# C_376p667.net
KiCad netlist of a schematic drawn in Altium Designer
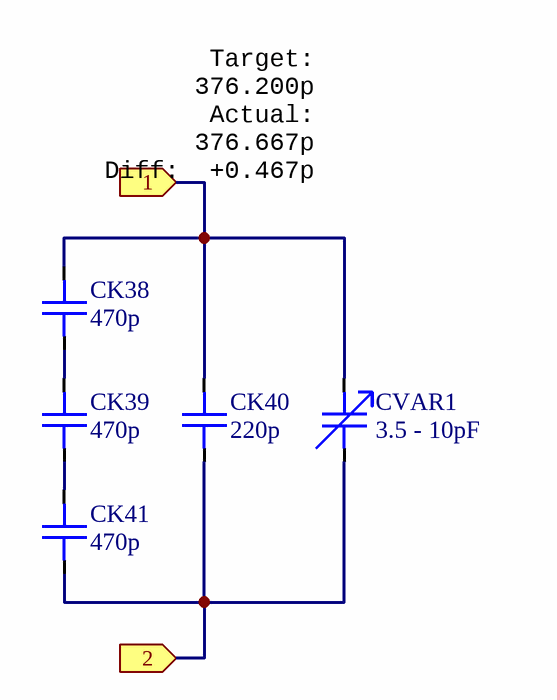
[diagram p0: C_376p667.SchDoc]

(export (version "E")
  (design (tool "Eeschema 10.0.6"))
  (components
    (comp (ref "CK38")
      (value "470p")
      (footprint "CAPC1005X06N(SMC0402)")
      (description "C; 470p; 50V; 1%; NP0/C0G; ??;")
      (fields (field (name "MANUFACTURER") "Kemet: C0402C471F5GAC7867;;Murata: GRM1555C1H471FA01D"))
      (libsource (lib "altium_sql") (part "CK"))
    )
    (comp (ref "CK39")
      (value "470p")
      (footprint "CAPC1005X06N(SMC0402)")
      (description "C; 470p; 50V; 1%; NP0/C0G; ??;")
      (fields (field (name "MANUFACTURER") "Kemet: C0402C471F5GAC7867;;Murata: GRM1555C1H471FA01D"))
      (libsource (lib "altium_sql") (part "CK"))
    )
    (comp (ref "CK40")
      (value "220p")
      (footprint "CAPC1005X06N(SMC0402)")
      (description "C; 220p; 50V; 1%; NP0/C0G; ??;")
      (fields (field (name "MANUFACTURER") "YAGEO: CC0402FRNPO9BN221"))
      (libsource (lib "altium_sql") (part "CK"))
    )
    (comp (ref "CK41")
      (value "470p")
      (footprint "CAPC1005X06N(SMC0402)")
      (description "C; 470p; 50V; 1%; NP0/C0G; ??;")
      (fields (field (name "MANUFACTURER") "Kemet: C0402C471F5GAC7867;;Murata: GRM1555C1H471FA01D"))
      (libsource (lib "altium_sql") (part "CK"))
    )
    (comp (ref "CVAR1")
      (value "3.5 - 10pF")
      (footprint "CTSC3S")
      (description "3.5 - 10pF, 50V")
      (libsource (lib "custom-footprints") (part "CTSC3S"))
    )
  )
  (nets
    (net (code "1") (name "/1") (class "Default")
      (node (ref "CK38") (pin "1") (pinfunction "1_1") (pintype "passive"))
      (node (ref "CK40") (pin "1") (pinfunction "1_1") (pintype "passive"))
      (node (ref "CVAR1") (pin "1") (pinfunction "1_1") (pintype "passive"))
    )
    (net (code "2") (name "/2") (class "Default")
      (node (ref "CK40") (pin "2") (pinfunction "2_2") (pintype "passive"))
      (node (ref "CK41") (pin "2") (pinfunction "2_2") (pintype "passive"))
      (node (ref "CVAR1") (pin "2") (pinfunction "2_2") (pintype "passive"))
    )
    (net (code "3") (name "Net-(CK38-Pad2)") (class "Default")
      (node (ref "CK38") (pin "2") (pinfunction "2_2") (pintype "passive"))
      (node (ref "CK39") (pin "1") (pinfunction "1_1") (pintype "passive"))
    )
    (net (code "4") (name "Net-(CK39-Pad2)") (class "Default")
      (node (ref "CK39") (pin "2") (pinfunction "2_2") (pintype "passive"))
      (node (ref "CK41") (pin "1") (pinfunction "1_1") (pintype "passive"))
    )
  )
)
